# OpAmp.net
KiCad netlist of a schematic drawn in Altium Designer
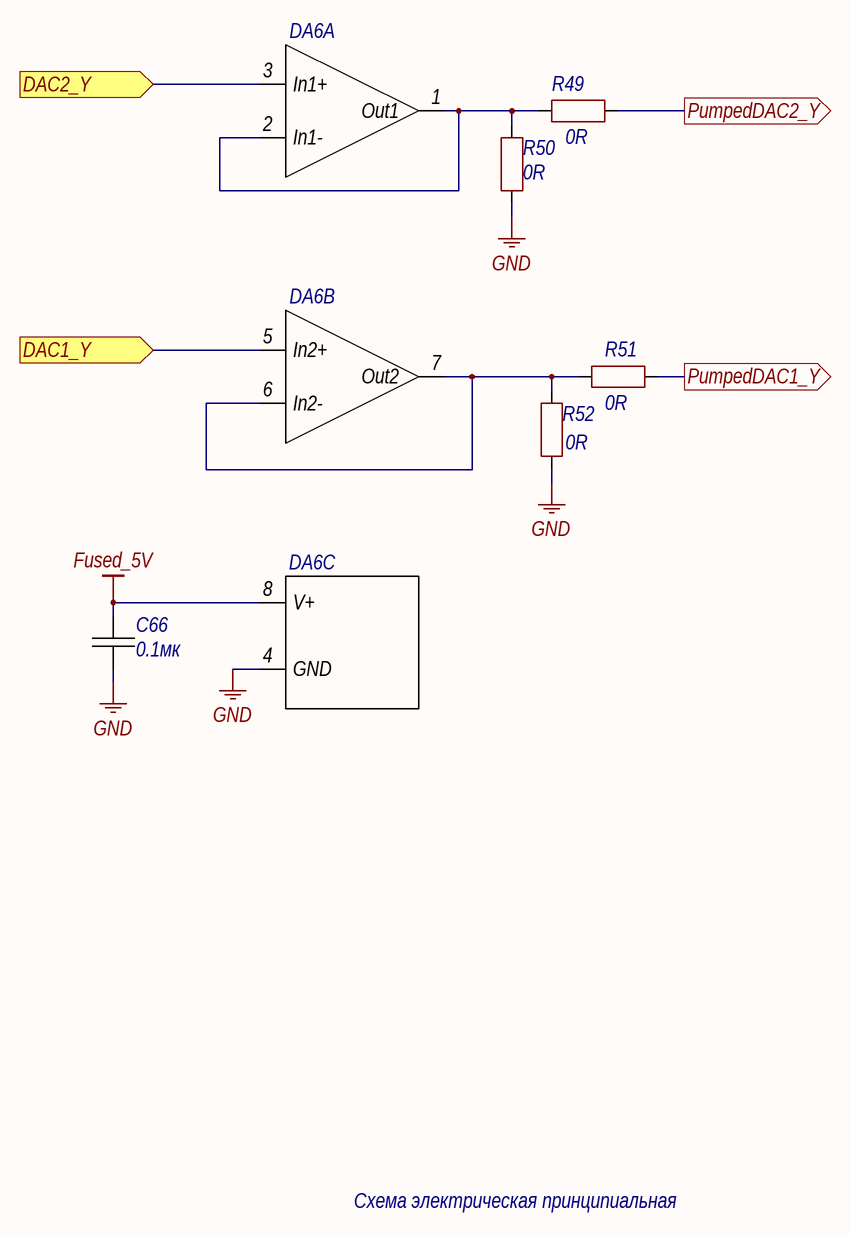
[diagram p0: OpAmp.SchDoc]

(export (version "E")
  (design (tool "Eeschema 10.0.6"))
  (components
    (comp (ref "C66")
      (value "0.1мк")
      (footprint "CAP0402")
      (fields
        (field (name "MANUFACTURER") "Samsung Electro-Mechanics")
        (field (name "MPN") "CL05B104KB54PNC")
        (field (name "TOLERANCE") "10%")
      )
      (libsource (lib "Library") (part "CAPC"))
    )
    (comp (ref "DA6")
      (value "AD8032ARZ")
      (footprint "SOIC-8_M")
      (fields (field (name "MANUFACTURER") "AD"))
      (libsource (lib "Library") (part "OpAmp_2_channels"))
    )
    (comp (ref "R49")
      (value "0R")
      (footprint "RESC0402(1005)_M")
      (fields (field (name "PART NUMBER") "RES0402") (field (name "Comment") "0R "))
      (libsource (lib "Library") (part "RES"))
    )
    (comp (ref "R50")
      (value "0R")
      (footprint "RESC0402(1005)_M")
      (fields (field (name "PART NUMBER") "RES0402") (field (name "Comment") "0R "))
      (libsource (lib "") (part "RES_1"))
    )
    (comp (ref "R51")
      (value "0R")
      (footprint "RESC0402(1005)_M")
      (fields (field (name "PART NUMBER") "RES0402") (field (name "Comment") "0R "))
      (libsource (lib "Library") (part "RES"))
    )
    (comp (ref "R52")
      (value "0R")
      (footprint "RESC0402(1005)_M")
      (fields (field (name "PART NUMBER") "RES0402") (field (name "Comment") "0R "))
      (libsource (lib "") (part "RES_1"))
    )
  )
  (nets
    (net (code "1") (name "/DAC1_Y") (class "Default")
      (node (ref "DA6") (pin "5") (pinfunction "In2+_5") (pintype "passive"))
    )
    (net (code "2") (name "/DAC2_Y") (class "Default")
      (node (ref "DA6") (pin "3") (pinfunction "In1+_3") (pintype "passive"))
    )
    (net (code "3") (name "/PumpedDAC1_Y") (class "Default")
      (node (ref "R51") (pin "1") (pinfunction "1_1") (pintype "passive"))
    )
    (net (code "4") (name "/PumpedDAC2_Y") (class "Default")
      (node (ref "R49") (pin "1") (pinfunction "1_1") (pintype "passive"))
    )
    (net (code "5") (name "Fused_5V") (class "Default")
      (node (ref "C66") (pin "2") (pinfunction "2_2") (pintype "passive"))
      (node (ref "DA6") (pin "8") (pinfunction "V+_8") (pintype "power_in"))
    )
    (net (code "6") (name "GND") (class "Default")
      (node (ref "C66") (pin "1") (pinfunction "1_1") (pintype "passive"))
      (node (ref "DA6") (pin "4") (pinfunction "GND_4") (pintype "power_in"))
      (node (ref "R50") (pin "1") (pinfunction "1_1") (pintype "passive"))
      (node (ref "R52") (pin "1") (pinfunction "1_1") (pintype "passive"))
    )
    (net (code "7") (name "Net-(DA6A-In1-)") (class "Default")
      (node (ref "DA6") (pin "1") (pinfunction "Out1_1") (pintype "passive"))
      (node (ref "DA6") (pin "2") (pinfunction "In1-_2") (pintype "passive"))
      (node (ref "R49") (pin "2") (pinfunction "2_2") (pintype "passive"))
      (node (ref "R50") (pin "2") (pinfunction "2_2") (pintype "passive"))
    )
    (net (code "8") (name "Net-(DA6B-In2-)") (class "Default")
      (node (ref "DA6") (pin "6") (pinfunction "In2-_6") (pintype "passive"))
      (node (ref "DA6") (pin "7") (pinfunction "Out2_7") (pintype "passive"))
      (node (ref "R51") (pin "2") (pinfunction "2_2") (pintype "passive"))
      (node (ref "R52") (pin "2") (pinfunction "2_2") (pintype "passive"))
    )
  )
)
